# T10_ChargerBase.net
KiCad netlist of a schematic drawn in EAGLE
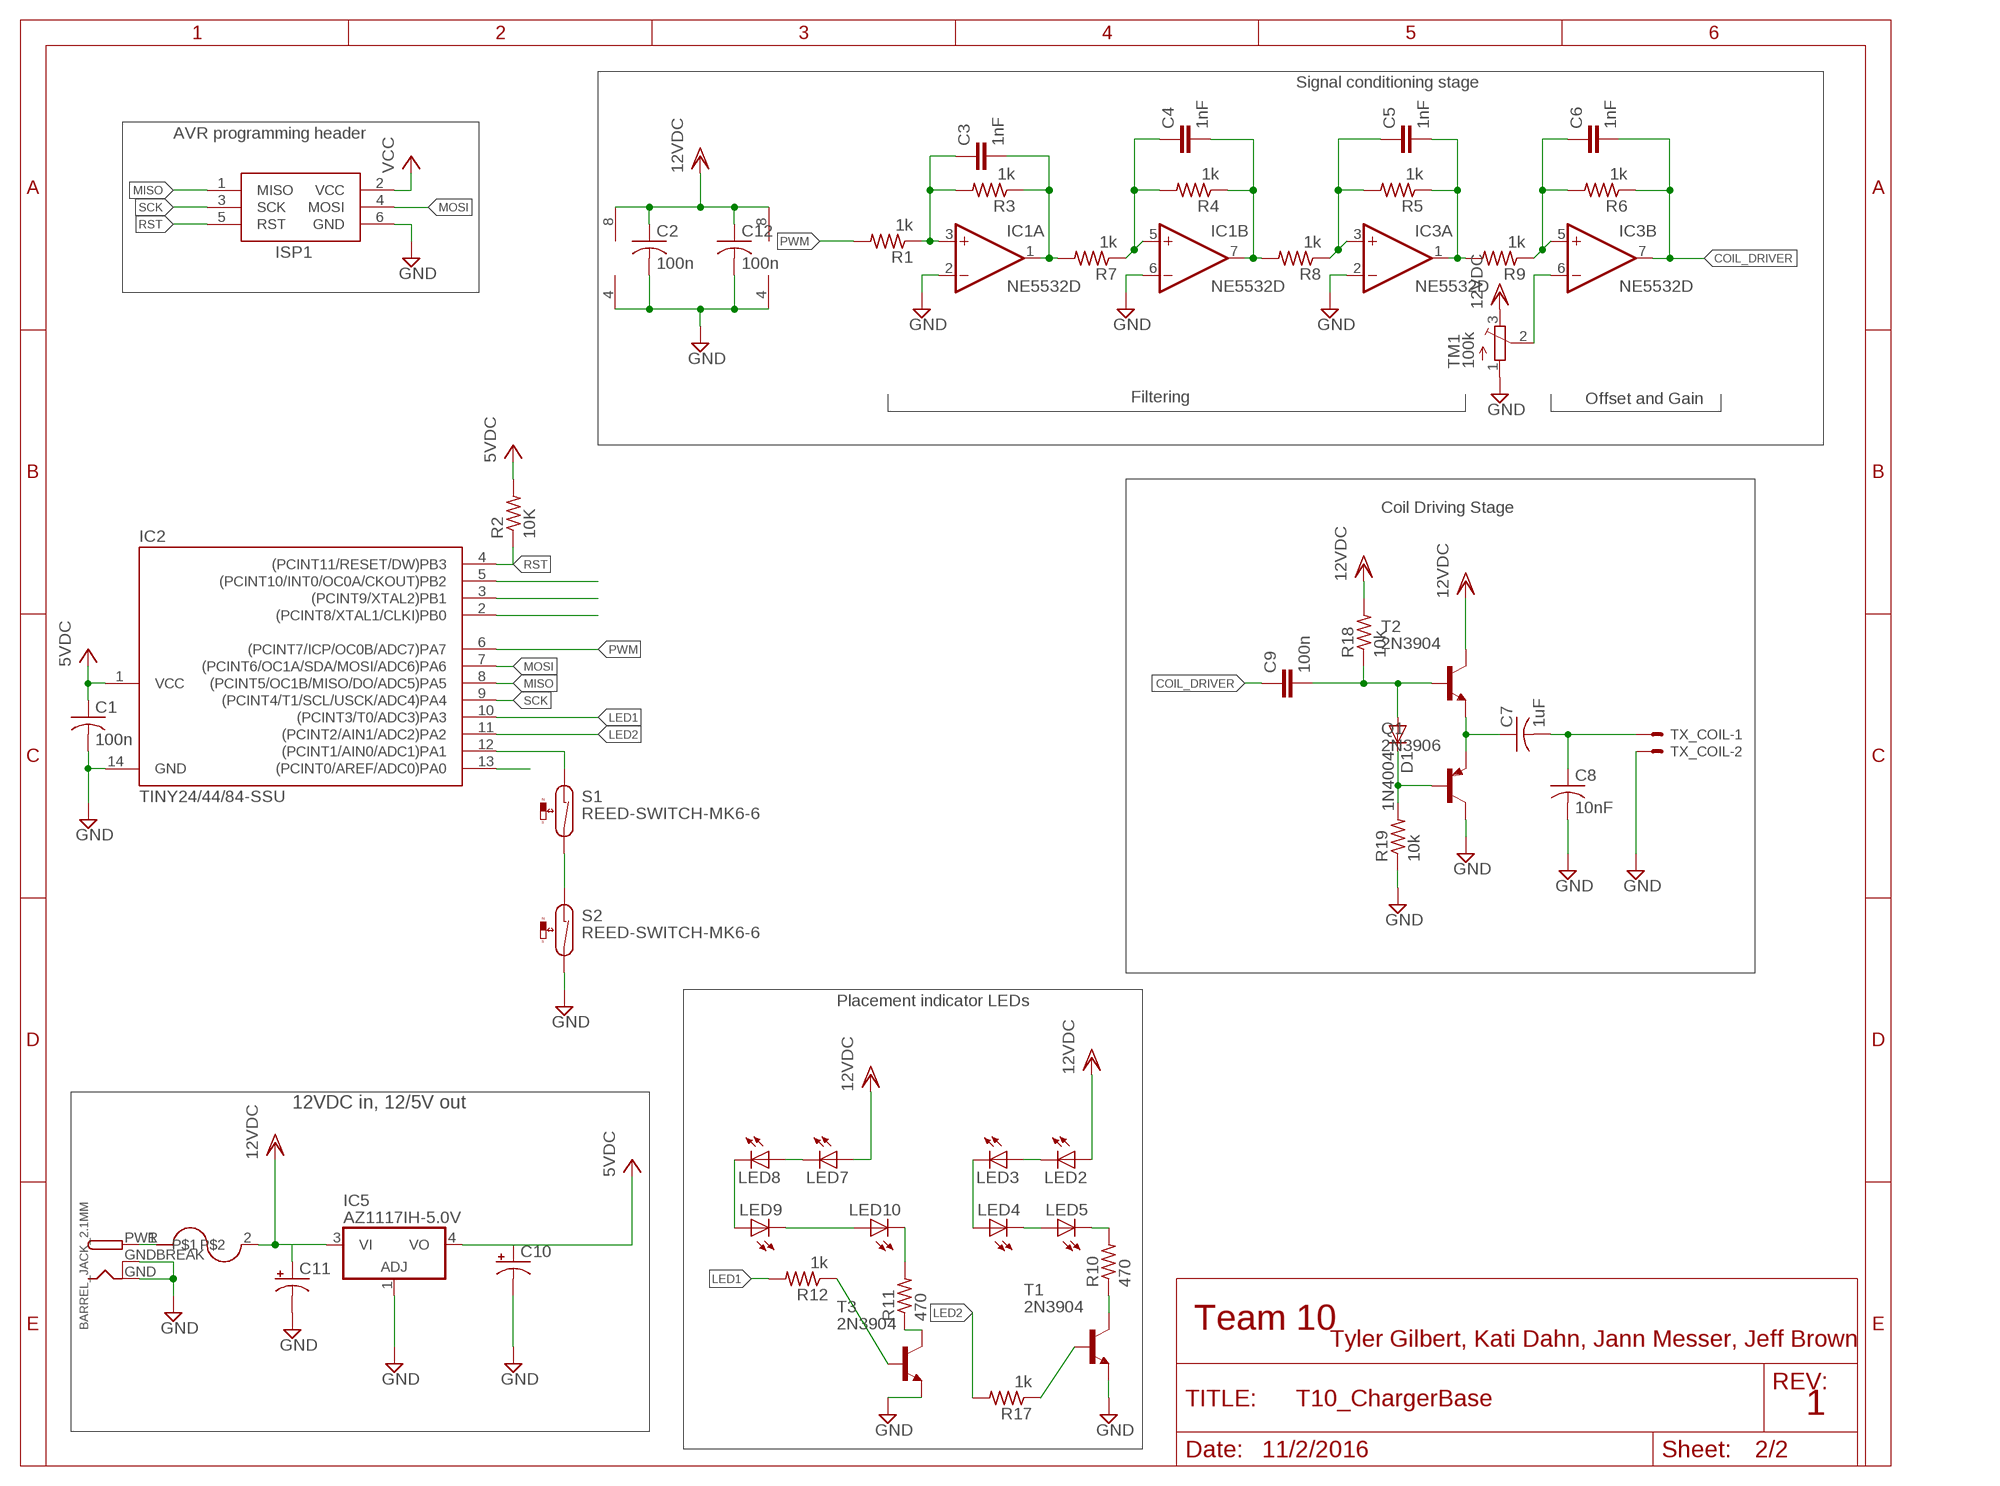
[diagram p0: schematic, sheet 1]

(export (version "E")
  (design (tool "Eeschema 10.0.6"))
  (components
    (comp (ref "BARREL_JACK_2.1MM")
      (value "DCBARRELPTH")
      (footprint "eagle-import:DCJACK_2MM_PTH")
      (libsource (lib "eagle-import") (part "DCBARRELPTH"))
    )
    (comp (ref "C1")
      (value "100n")
      (footprint "eagle-import:C0805")
      (libsource (lib "eagle-import") (part "rcl_C-USC0805"))
    )
    (comp (ref "C2")
      (value "100n")
      (footprint "eagle-import:C0805")
      (libsource (lib "eagle-import") (part "rcl_C-USC0805"))
    )
    (comp (ref "C3")
      (value "1nF")
      (footprint "eagle-import:C0805")
      (libsource (lib "eagle-import") (part "C-EUC0805"))
    )
    (comp (ref "C4")
      (value "1nF")
      (footprint "eagle-import:C0805")
      (libsource (lib "eagle-import") (part "C-EUC0805"))
    )
    (comp (ref "C5")
      (value "1nF")
      (footprint "eagle-import:C0805")
      (libsource (lib "eagle-import") (part "C-EUC0805"))
    )
    (comp (ref "C6")
      (value "1nF")
      (footprint "eagle-import:C0805")
      (libsource (lib "eagle-import") (part "C-EUC0805"))
    )
    (comp (ref "C7")
      (value "1uF")
      (footprint "eagle-import:C050-025X075")
      (libsource (lib "eagle-import") (part "C-US050-025X075"))
    )
    (comp (ref "C8")
      (value "10nF")
      (footprint "eagle-import:C050-025X075")
      (libsource (lib "eagle-import") (part "C-US050-025X075"))
    )
    (comp (ref "C9")
      (value "100n")
      (footprint "eagle-import:C0805")
      (libsource (lib "eagle-import") (part "C-EUC0805"))
    )
    (comp (ref "C10")
      (value "CPOL-USE2-5")
      (footprint "eagle-import:E2-5")
      (libsource (lib "eagle-import") (part "CPOL-USE2-5"))
    )
    (comp (ref "C11")
      (value "CPOL-USE2-5")
      (footprint "eagle-import:E2-5")
      (libsource (lib "eagle-import") (part "CPOL-USE2-5"))
    )
    (comp (ref "C12")
      (value "100n")
      (footprint "eagle-import:C0805")
      (libsource (lib "eagle-import") (part "rcl_C-USC0805"))
    )
    (comp (ref "D1")
      (value "1N4004")
      (footprint "eagle-import:DO41-10")
      (libsource (lib "eagle-import") (part "1N4004"))
    )
    (comp (ref "IC1")
      (value "NE5532D")
      (footprint "eagle-import:SO08")
      (libsource (lib "eagle-import") (part "NE5532D"))
    )
    (comp (ref "IC2")
      (value "TINY24/44/84-SSU")
      (footprint "eagle-import:SOIC14")
      (libsource (lib "eagle-import") (part "TINY24/44/84-SSU"))
    )
    (comp (ref "IC3")
      (value "NE5532D")
      (footprint "eagle-import:SO08")
      (libsource (lib "eagle-import") (part "NE5532D"))
    )
    (comp (ref "IC5")
      (value "AZ1117IH-5.0V")
      (footprint "eagle-import:SOT223")
      (libsource (lib "eagle-import") (part "317EMP"))
    )
    (comp (ref "ISP1")
      (value "AVRISP-6")
      (footprint "eagle-import:AVRISP")
      (libsource (lib "eagle-import") (part "AVRISP-6"))
    )
    (comp (ref "LED2")
      (value "LEDCHIPLED_0805")
      (footprint "eagle-import:CHIPLED_0805")
      (libsource (lib "eagle-import") (part "LEDCHIPLED_0805"))
    )
    (comp (ref "LED3")
      (value "LEDCHIPLED_0805")
      (footprint "eagle-import:CHIPLED_0805")
      (libsource (lib "eagle-import") (part "LEDCHIPLED_0805"))
    )
    (comp (ref "LED4")
      (value "LEDCHIPLED_0805")
      (footprint "eagle-import:CHIPLED_0805")
      (libsource (lib "eagle-import") (part "LEDCHIPLED_0805"))
    )
    (comp (ref "LED5")
      (value "LEDCHIPLED_0805")
      (footprint "eagle-import:CHIPLED_0805")
      (libsource (lib "eagle-import") (part "LEDCHIPLED_0805"))
    )
    (comp (ref "LED7")
      (value "LEDCHIPLED_0805")
      (footprint "eagle-import:CHIPLED_0805")
      (libsource (lib "eagle-import") (part "LEDCHIPLED_0805"))
    )
    (comp (ref "LED8")
      (value "LEDCHIPLED_0805")
      (footprint "eagle-import:CHIPLED_0805")
      (libsource (lib "eagle-import") (part "LEDCHIPLED_0805"))
    )
    (comp (ref "LED9")
      (value "LEDCHIPLED_0805")
      (footprint "eagle-import:CHIPLED_0805")
      (libsource (lib "eagle-import") (part "LEDCHIPLED_0805"))
    )
    (comp (ref "LED10")
      (value "LEDCHIPLED_0805")
      (footprint "eagle-import:CHIPLED_0805")
      (libsource (lib "eagle-import") (part "LEDCHIPLED_0805"))
    )
    (comp (ref "Q1")
      (value "2N3906")
      (footprint "eagle-import:TO92")
      (libsource (lib "eagle-import") (part "2N3906"))
    )
    (comp (ref "R1")
      (value "1k")
      (footprint "eagle-import:R0805")
      (libsource (lib "eagle-import") (part "R-US_R0805"))
    )
    (comp (ref "R2")
      (value "10K")
      (footprint "eagle-import:R0805")
      (libsource (lib "eagle-import") (part "R-US_R0805"))
    )
    (comp (ref "R3")
      (value "1k")
      (footprint "eagle-import:R0805")
      (libsource (lib "eagle-import") (part "R-US_R0805"))
    )
    (comp (ref "R4")
      (value "1k")
      (footprint "eagle-import:R0805")
      (libsource (lib "eagle-import") (part "R-US_R0805"))
    )
    (comp (ref "R5")
      (value "1k")
      (footprint "eagle-import:R0805")
      (libsource (lib "eagle-import") (part "R-US_R0805"))
    )
    (comp (ref "R6")
      (value "1k")
      (footprint "eagle-import:R0805")
      (libsource (lib "eagle-import") (part "R-US_R0805"))
    )
    (comp (ref "R7")
      (value "1k")
      (footprint "eagle-import:R0805")
      (libsource (lib "eagle-import") (part "R-US_R0805"))
    )
    (comp (ref "R8")
      (value "1k")
      (footprint "eagle-import:R0805")
      (libsource (lib "eagle-import") (part "R-US_R0805"))
    )
    (comp (ref "R9")
      (value "1k")
      (footprint "eagle-import:R0805")
      (libsource (lib "eagle-import") (part "R-US_R0805"))
    )
    (comp (ref "R10")
      (value "470")
      (footprint "eagle-import:R0805")
      (libsource (lib "eagle-import") (part "R-US_R0805"))
    )
    (comp (ref "R11")
      (value "470")
      (footprint "eagle-import:R0805")
      (libsource (lib "eagle-import") (part "R-US_R0805"))
    )
    (comp (ref "R12")
      (value "1k")
      (footprint "eagle-import:R0805")
      (libsource (lib "eagle-import") (part "R-US_R0805"))
    )
    (comp (ref "R17")
      (value "1k")
      (footprint "eagle-import:R0805")
      (libsource (lib "eagle-import") (part "R-US_R0805"))
    )
    (comp (ref "R18")
      (value "10k")
      (footprint "eagle-import:R0805")
      (libsource (lib "eagle-import") (part "R-US_R0805"))
    )
    (comp (ref "R19")
      (value "10k")
      (footprint "eagle-import:R0805")
      (libsource (lib "eagle-import") (part "R-US_R0805"))
    )
    (comp (ref "S1")
      (value "REED-SWITCH-MK6-6")
      (footprint "eagle-import:MK6-6")
      (libsource (lib "eagle-import") (part "REED-SWITCH-MK6-6"))
    )
    (comp (ref "S2")
      (value "REED-SWITCH-MK6-6")
      (footprint "eagle-import:MK6-6")
      (libsource (lib "eagle-import") (part "REED-SWITCH-MK6-6"))
    )
    (comp (ref "T1")
      (value "2N3904")
      (footprint "eagle-import:TO92")
      (libsource (lib "eagle-import") (part "2N3904"))
    )
    (comp (ref "T2")
      (value "2N3904")
      (footprint "eagle-import:TO92")
      (libsource (lib "eagle-import") (part "2N3904"))
    )
    (comp (ref "T3")
      (value "2N3904")
      (footprint "eagle-import:TO92")
      (libsource (lib "eagle-import") (part "2N3904"))
    )
    (comp (ref "TM1")
      (value "100k")
      (footprint "eagle-import:TC33X")
      (libsource (lib "eagle-import") (part "TRIMPOTTC33X"))
    )
    (comp (ref "TX_COIL")
      (value "22-23-2021")
      (footprint "eagle-import:22-23-2021")
      (fields (field (name "MF") "MOLEX"))
      (libsource (lib "eagle-import") (part "22-23-2021"))
    )
    (comp (ref "U$1")
      (value "LITTLEFUSE")
      (footprint "eagle-import:LITTLEFUSE")
      (libsource (lib "eagle-import") (part "LITTLEFUSE"))
    )
  )
  (nets
    (net (code "1") (name "5VDC") (class "Default")
      (node (ref "C1") (pin "1") (pinfunction "1_1") (pintype "passive"))
      (node (ref "C10") (pin "+") (pinfunction "+_+") (pintype "passive"))
      (node (ref "IC2") (pin "1") (pinfunction "VCC_1") (pintype "power_in"))
      (node (ref "IC5") (pin "4") (pinfunction "VO_4") (pintype "passive"))
      (node (ref "ISP1") (pin "2") (pinfunction "VCC_2") (pintype "power_in"))
      (node (ref "R2") (pin "2") (pinfunction "2_2") (pintype "passive"))
    )
    (net (code "2") (name "12VDC") (class "Default")
      (node (ref "C11") (pin "+") (pinfunction "+_+") (pintype "passive"))
      (node (ref "C12") (pin "1") (pinfunction "1_1") (pintype "passive"))
      (node (ref "C2") (pin "1") (pinfunction "1_1") (pintype "passive"))
      (node (ref "IC1") (pin "8") (pinfunction "V+_8") (pintype "power_in"))
      (node (ref "IC3") (pin "8") (pinfunction "V+_8") (pintype "power_in"))
      (node (ref "IC5") (pin "3") (pinfunction "VI_3") (pintype "input"))
      (node (ref "LED2") (pin "A") (pinfunction "A_A") (pintype "passive"))
      (node (ref "LED7") (pin "A") (pinfunction "A_A") (pintype "passive"))
      (node (ref "R18") (pin "2") (pinfunction "2_2") (pintype "passive"))
      (node (ref "T2") (pin "1") (pinfunction "C_1") (pintype "passive"))
      (node (ref "TM1") (pin "3") (pinfunction "E_3") (pintype "passive"))
      (node (ref "U$1") (pin "2") (pinfunction "P$2_2") (pintype "bidirectional"))
    )
    (net (code "3") (name "COIL_DRIVER") (class "Default")
      (node (ref "C6") (pin "2") (pinfunction "2_2") (pintype "passive"))
      (node (ref "C9") (pin "1") (pinfunction "1_1") (pintype "passive"))
      (node (ref "IC3") (pin "7") (pinfunction "OUT_7") (pintype "output"))
      (node (ref "R6") (pin "1") (pinfunction "1_1") (pintype "passive"))
    )
    (net (code "4") (name "GND") (class "Default")
      (node (ref "BARREL_JACK_2.1MM") (pin "GND") (pinfunction "GND_GND") (pintype "power_in"))
      (node (ref "BARREL_JACK_2.1MM") (pin "GNDBREAK") (pinfunction "GNDBREAK_GNDBREAK") (pintype "power_in"))
      (node (ref "C1") (pin "2") (pinfunction "2_2") (pintype "passive"))
      (node (ref "C10") (pin "-") (pinfunction "-_-") (pintype "passive"))
      (node (ref "C11") (pin "-") (pinfunction "-_-") (pintype "passive"))
      (node (ref "C12") (pin "2") (pinfunction "2_2") (pintype "passive"))
      (node (ref "C2") (pin "2") (pinfunction "2_2") (pintype "passive"))
      (node (ref "C8") (pin "2") (pinfunction "2_2") (pintype "passive"))
      (node (ref "IC1") (pin "2") (pinfunction "-IN_2") (pintype "input"))
      (node (ref "IC1") (pin "4") (pinfunction "V-_4") (pintype "power_in"))
      (node (ref "IC1") (pin "6") (pinfunction "-IN_6") (pintype "input"))
      (node (ref "IC2") (pin "14") (pinfunction "GND_14") (pintype "power_in"))
      (node (ref "IC3") (pin "2") (pinfunction "-IN_2") (pintype "input"))
      (node (ref "IC3") (pin "4") (pinfunction "V-_4") (pintype "power_in"))
      (node (ref "IC5") (pin "1") (pinfunction "ADJ_1") (pintype "input"))
      (node (ref "ISP1") (pin "6") (pinfunction "GND_6") (pintype "power_in"))
      (node (ref "Q1") (pin "1") (pinfunction "C_1") (pintype "passive"))
      (node (ref "R19") (pin "1") (pinfunction "1_1") (pintype "passive"))
      (node (ref "S2") (pin "2") (pinfunction "2_2") (pintype "passive"))
      (node (ref "T1") (pin "3") (pinfunction "E_3") (pintype "passive"))
      (node (ref "T3") (pin "3") (pinfunction "E_3") (pintype "passive"))
      (node (ref "TM1") (pin "1") (pinfunction "A_1") (pintype "passive"))
      (node (ref "TX_COIL") (pin "2") (pinfunction "S_2") (pintype "passive"))
    )
    (net (code "5") (name "LED1") (class "Default")
      (node (ref "IC2") (pin "10") (pinfunction "(PCINT3/T0/ADC3)PA3_10") (pintype "bidirectional"))
      (node (ref "R12") (pin "2") (pinfunction "2_2") (pintype "passive"))
    )
    (net (code "6") (name "LED2") (class "Default")
      (node (ref "IC2") (pin "11") (pinfunction "(PCINT2/AIN1/ADC2)PA2_11") (pintype "bidirectional"))
      (node (ref "R17") (pin "2") (pinfunction "2_2") (pintype "passive"))
    )
    (net (code "7") (name "MISO") (class "Default")
      (node (ref "IC2") (pin "8") (pinfunction "(PCINT5/OC1B/MISO/DO/ADC5)PA5_8") (pintype "bidirectional"))
      (node (ref "ISP1") (pin "1") (pinfunction "MISO_1") (pintype "input"))
    )
    (net (code "8") (name "MOSI") (class "Default")
      (node (ref "IC2") (pin "7") (pinfunction "(PCINT6/OC1A/SDA/MOSI/ADC6)PA6_7") (pintype "bidirectional"))
      (node (ref "ISP1") (pin "4") (pinfunction "MOSI_4") (pintype "output"))
    )
    (net (code "9") (name "Net-(IC1A-+IN)") (class "Default")
      (node (ref "C3") (pin "1") (pinfunction "1_1") (pintype "passive"))
      (node (ref "IC1") (pin "3") (pinfunction "+IN_3") (pintype "input"))
      (node (ref "R1") (pin "1") (pinfunction "1_1") (pintype "passive"))
      (node (ref "R3") (pin "2") (pinfunction "2_2") (pintype "passive"))
    )
    (net (code "10") (name "Net-(IC1A-OUT)") (class "Default")
      (node (ref "C3") (pin "2") (pinfunction "2_2") (pintype "passive"))
      (node (ref "IC1") (pin "1") (pinfunction "OUT_1") (pintype "output"))
      (node (ref "R3") (pin "1") (pinfunction "1_1") (pintype "passive"))
      (node (ref "R7") (pin "2") (pinfunction "2_2") (pintype "passive"))
    )
    (net (code "11") (name "Net-(IC1B-+IN)") (class "Default")
      (node (ref "C4") (pin "1") (pinfunction "1_1") (pintype "passive"))
      (node (ref "IC1") (pin "5") (pinfunction "+IN_5") (pintype "input"))
      (node (ref "R4") (pin "2") (pinfunction "2_2") (pintype "passive"))
      (node (ref "R7") (pin "1") (pinfunction "1_1") (pintype "passive"))
    )
    (net (code "12") (name "Net-(IC1B-OUT)") (class "Default")
      (node (ref "C4") (pin "2") (pinfunction "2_2") (pintype "passive"))
      (node (ref "IC1") (pin "7") (pinfunction "OUT_7") (pintype "output"))
      (node (ref "R4") (pin "1") (pinfunction "1_1") (pintype "passive"))
      (node (ref "R8") (pin "2") (pinfunction "2_2") (pintype "passive"))
    )
    (net (code "13") (name "Net-(IC2-(PCINT1{slash}AIN0{slash}ADC1)PA1)") (class "Default")
      (node (ref "IC2") (pin "12") (pinfunction "(PCINT1/AIN0/ADC1)PA1_12") (pintype "bidirectional"))
      (node (ref "S1") (pin "1") (pinfunction "1_1") (pintype "passive"))
    )
    (net (code "14") (name "Net-(IC3A-+IN)") (class "Default")
      (node (ref "C5") (pin "1") (pinfunction "1_1") (pintype "passive"))
      (node (ref "IC3") (pin "3") (pinfunction "+IN_3") (pintype "input"))
      (node (ref "R5") (pin "2") (pinfunction "2_2") (pintype "passive"))
      (node (ref "R8") (pin "1") (pinfunction "1_1") (pintype "passive"))
    )
    (net (code "15") (name "Net-(IC3A-OUT)") (class "Default")
      (node (ref "C5") (pin "2") (pinfunction "2_2") (pintype "passive"))
      (node (ref "IC3") (pin "1") (pinfunction "OUT_1") (pintype "output"))
      (node (ref "R5") (pin "1") (pinfunction "1_1") (pintype "passive"))
      (node (ref "R9") (pin "2") (pinfunction "2_2") (pintype "passive"))
    )
    (net (code "16") (name "Net-(IC3B-+IN)") (class "Default")
      (node (ref "C6") (pin "1") (pinfunction "1_1") (pintype "passive"))
      (node (ref "IC3") (pin "5") (pinfunction "+IN_5") (pintype "input"))
      (node (ref "R6") (pin "2") (pinfunction "2_2") (pintype "passive"))
      (node (ref "R9") (pin "1") (pinfunction "1_1") (pintype "passive"))
    )
    (net (code "17") (name "Net-(IC3B--IN)") (class "Default")
      (node (ref "IC3") (pin "6") (pinfunction "-IN_6") (pintype "input"))
      (node (ref "TM1") (pin "2") (pinfunction "S_2") (pintype "passive"))
    )
    (net (code "18") (name "Net-(LED2-PadC)") (class "Default")
      (node (ref "LED2") (pin "C") (pinfunction "C_C") (pintype "passive"))
      (node (ref "LED3") (pin "A") (pinfunction "A_A") (pintype "passive"))
    )
    (net (code "19") (name "Net-(LED3-PadC)") (class "Default")
      (node (ref "LED3") (pin "C") (pinfunction "C_C") (pintype "passive"))
      (node (ref "LED4") (pin "A") (pinfunction "A_A") (pintype "passive"))
    )
    (net (code "20") (name "Net-(LED4-PadC)") (class "Default")
      (node (ref "LED4") (pin "C") (pinfunction "C_C") (pintype "passive"))
      (node (ref "LED5") (pin "A") (pinfunction "A_A") (pintype "passive"))
    )
    (net (code "21") (name "Net-(LED5-PadC)") (class "Default")
      (node (ref "LED5") (pin "C") (pinfunction "C_C") (pintype "passive"))
      (node (ref "R10") (pin "2") (pinfunction "2_2") (pintype "passive"))
    )
    (net (code "22") (name "Net-(LED7-PadC)") (class "Default")
      (node (ref "LED7") (pin "C") (pinfunction "C_C") (pintype "passive"))
      (node (ref "LED8") (pin "A") (pinfunction "A_A") (pintype "passive"))
    )
    (net (code "23") (name "Net-(LED8-PadC)") (class "Default")
      (node (ref "LED8") (pin "C") (pinfunction "C_C") (pintype "passive"))
      (node (ref "LED9") (pin "A") (pinfunction "A_A") (pintype "passive"))
    )
    (net (code "24") (name "Net-(LED10-PadA)") (class "Default")
      (node (ref "LED10") (pin "A") (pinfunction "A_A") (pintype "passive"))
      (node (ref "LED9") (pin "C") (pinfunction "C_C") (pintype "passive"))
    )
    (net (code "25") (name "Net-(LED10-PadC)") (class "Default")
      (node (ref "LED10") (pin "C") (pinfunction "C_C") (pintype "passive"))
      (node (ref "R11") (pin "2") (pinfunction "2_2") (pintype "passive"))
    )
    (net (code "26") (name "Net-(Q1-B)") (class "Default")
      (node (ref "D1") (pin "C") (pinfunction "C_C") (pintype "passive"))
      (node (ref "Q1") (pin "2") (pinfunction "B_2") (pintype "passive"))
      (node (ref "R19") (pin "2") (pinfunction "2_2") (pintype "passive"))
    )
    (net (code "27") (name "Net-(Q1-E)") (class "Default")
      (node (ref "C7") (pin "1") (pinfunction "1_1") (pintype "passive"))
      (node (ref "Q1") (pin "3") (pinfunction "E_3") (pintype "passive"))
      (node (ref "T2") (pin "3") (pinfunction "E_3") (pintype "passive"))
    )
    (net (code "28") (name "Net-(S1-Pad2)") (class "Default")
      (node (ref "S1") (pin "2") (pinfunction "2_2") (pintype "passive"))
      (node (ref "S2") (pin "1") (pinfunction "1_1") (pintype "passive"))
    )
    (net (code "29") (name "Net-(T1-B)") (class "Default")
      (node (ref "R17") (pin "1") (pinfunction "1_1") (pintype "passive"))
      (node (ref "T1") (pin "2") (pinfunction "B_2") (pintype "passive"))
    )
    (net (code "30") (name "Net-(T1-C)") (class "Default")
      (node (ref "R10") (pin "1") (pinfunction "1_1") (pintype "passive"))
      (node (ref "T1") (pin "1") (pinfunction "C_1") (pintype "passive"))
    )
    (net (code "31") (name "Net-(T2-B)") (class "Default")
      (node (ref "C9") (pin "2") (pinfunction "2_2") (pintype "passive"))
      (node (ref "D1") (pin "A") (pinfunction "A_A") (pintype "passive"))
      (node (ref "R18") (pin "1") (pinfunction "1_1") (pintype "passive"))
      (node (ref "T2") (pin "2") (pinfunction "B_2") (pintype "passive"))
    )
    (net (code "32") (name "Net-(T3-B)") (class "Default")
      (node (ref "R12") (pin "1") (pinfunction "1_1") (pintype "passive"))
      (node (ref "T3") (pin "2") (pinfunction "B_2") (pintype "passive"))
    )
    (net (code "33") (name "Net-(T3-C)") (class "Default")
      (node (ref "R11") (pin "1") (pinfunction "1_1") (pintype "passive"))
      (node (ref "T3") (pin "1") (pinfunction "C_1") (pintype "passive"))
    )
    (net (code "34") (name "Net-(TX_COILA-S)") (class "Default")
      (node (ref "C7") (pin "2") (pinfunction "2_2") (pintype "passive"))
      (node (ref "C8") (pin "1") (pinfunction "1_1") (pintype "passive"))
      (node (ref "TX_COIL") (pin "1") (pinfunction "S_1") (pintype "passive"))
    )
    (net (code "35") (name "Net-(U$1-P$1)") (class "Default")
      (node (ref "BARREL_JACK_2.1MM") (pin "PWR") (pinfunction "PWR_PWR") (pintype "power_in"))
      (node (ref "U$1") (pin "1") (pinfunction "P$1_1") (pintype "bidirectional"))
    )
    (net (code "36") (name "PWM") (class "Default")
      (node (ref "IC2") (pin "6") (pinfunction "(PCINT7/ICP/OC0B/ADC7)PA7_6") (pintype "bidirectional"))
      (node (ref "R1") (pin "2") (pinfunction "2_2") (pintype "passive"))
    )
    (net (code "37") (name "RST") (class "Default")
      (node (ref "IC2") (pin "4") (pinfunction "(PCINT11/RESET/DW)PB3_4") (pintype "bidirectional"))
      (node (ref "ISP1") (pin "5") (pinfunction "RST_5") (pintype "output"))
      (node (ref "R2") (pin "1") (pinfunction "1_1") (pintype "passive"))
    )
    (net (code "38") (name "SCK") (class "Default")
      (node (ref "IC2") (pin "9") (pinfunction "(PCINT4/T1/SCL/USCK/ADC4)PA4_9") (pintype "bidirectional"))
      (node (ref "ISP1") (pin "3") (pinfunction "SCK_3") (pintype "output"))
    )
    (net (code "39") (name "unconnected-(IC2-(PCINT0{slash}AREF{slash}ADC0)PA0-Pad13)") (class "Default")
      (node (ref "IC2") (pin "13") (pinfunction "(PCINT0/AREF/ADC0)PA0_13") (pintype "bidirectional"))
    )
    (net (code "40") (name "unconnected-(IC2-(PCINT8{slash}XTAL1{slash}CLKI)PB0-Pad2)") (class "Default")
      (node (ref "IC2") (pin "2") (pinfunction "(PCINT8/XTAL1/CLKI)PB0_2") (pintype "bidirectional"))
    )
    (net (code "41") (name "unconnected-(IC2-(PCINT9{slash}XTAL2)PB1-Pad3)") (class "Default")
      (node (ref "IC2") (pin "3") (pinfunction "(PCINT9/XTAL2)PB1_3") (pintype "bidirectional"))
    )
    (net (code "42") (name "unconnected-(IC2-(PCINT10{slash}INT0{slash}OC0A{slash}CKOUT)PB2-Pad5)") (class "Default")
      (node (ref "IC2") (pin "5") (pinfunction "(PCINT10/INT0/OC0A/CKOUT)PB2_5") (pintype "bidirectional"))
    )
  )
)
